# analog.net
KiCad netlist of a schematic drawn in EAGLE
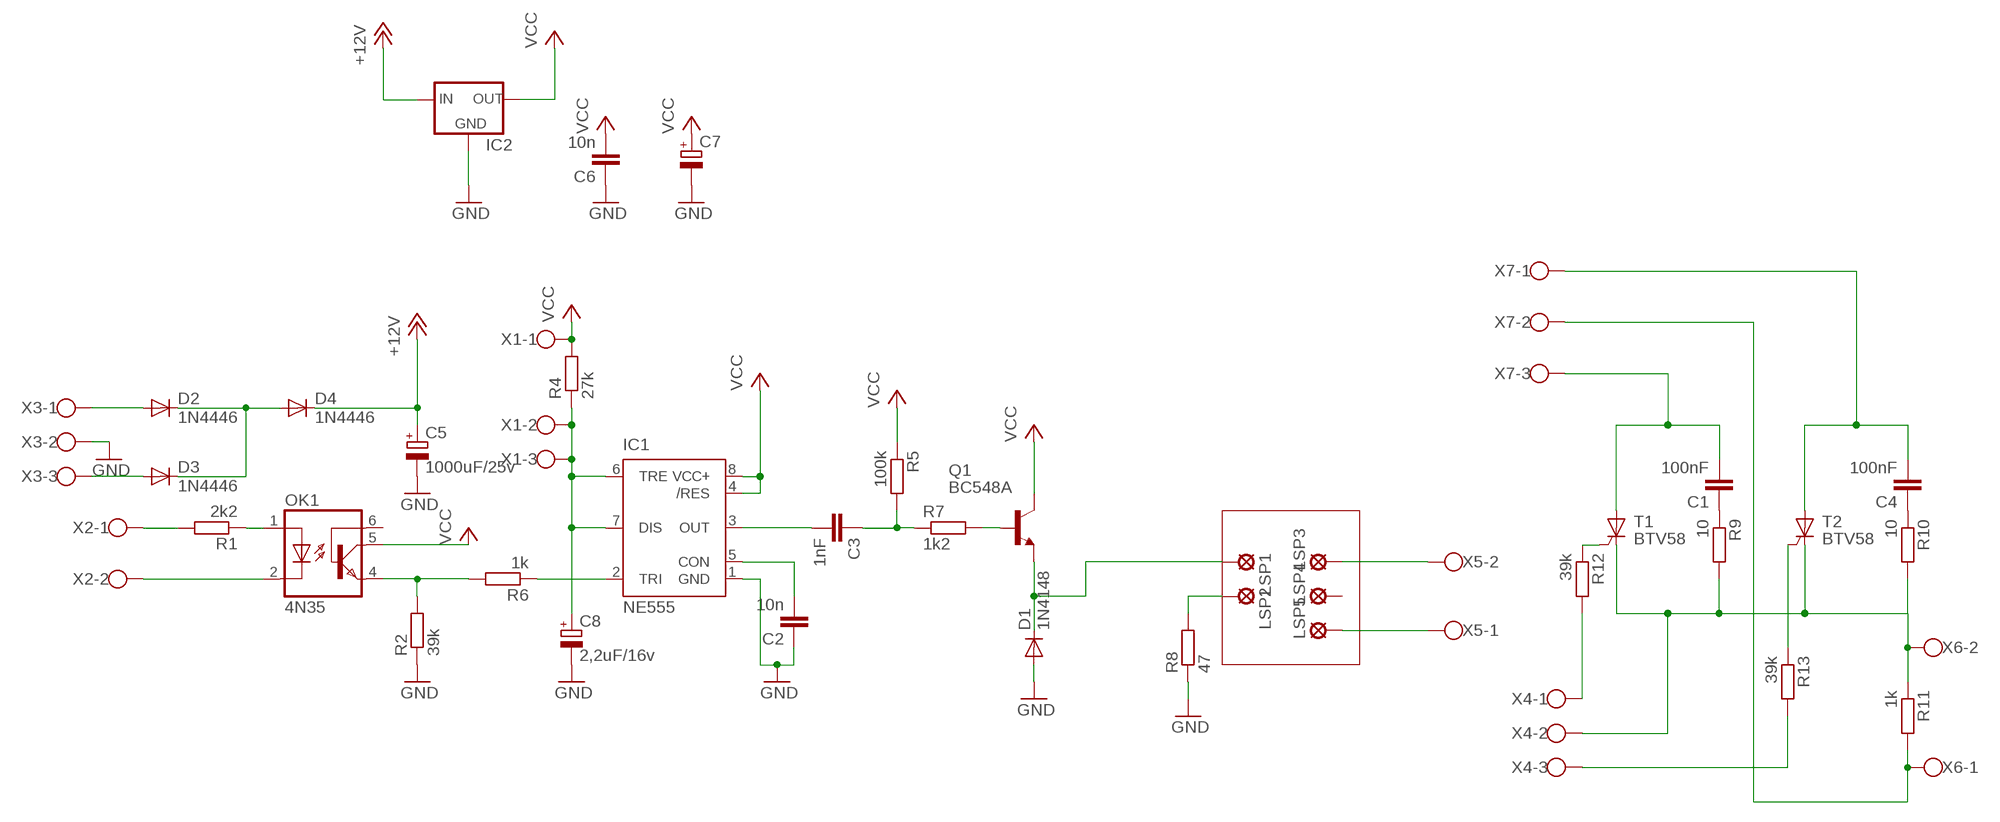
[diagram p0: schematic, sheet 1]

(export (version "E")
  (design (tool "Eeschema 10.0.6"))
  (components
    (comp (ref "C1")
      (value "100nF")
      (footprint "eagle-import:C050-025X075")
      (libsource (lib "eagle-import") (part "C-EU050-025X075"))
    )
    (comp (ref "C2")
      (value "10n")
      (footprint "eagle-import:C050-025X075")
      (libsource (lib "eagle-import") (part "C-EU050-025X075"))
    )
    (comp (ref "C3")
      (value "1nF")
      (footprint "eagle-import:C050-025X075")
      (libsource (lib "eagle-import") (part "C-EU050-025X075"))
    )
    (comp (ref "C4")
      (value "100nF")
      (footprint "eagle-import:C050-025X075")
      (libsource (lib "eagle-import") (part "C-EU050-025X075"))
    )
    (comp (ref "C5")
      (value "1000uF/25v")
      (footprint "eagle-import:E5-8,5")
      (libsource (lib "eagle-import") (part "CPOL-EUE5-8.5"))
    )
    (comp (ref "C6")
      (value "10n")
      (footprint "eagle-import:C050-025X075")
      (libsource (lib "eagle-import") (part "C-EU050-025X075"))
    )
    (comp (ref "C7")
      (value "CPOL-EUE2.5-5")
      (footprint "eagle-import:E2,5-5")
      (libsource (lib "eagle-import") (part "CPOL-EUE2.5-5"))
    )
    (comp (ref "C8")
      (value "2,2uF/16v")
      (footprint "eagle-import:E2,5-5")
      (libsource (lib "eagle-import") (part "CPOL-EUE2.5-5"))
    )
    (comp (ref "D1")
      (value "1N4148")
      (footprint "eagle-import:DO35-10")
      (libsource (lib "eagle-import") (part "1N4148DO35-10"))
    )
    (comp (ref "D2")
      (value "1N4446")
      (footprint "eagle-import:DO35-10")
      (libsource (lib "eagle-import") (part "1N4446"))
    )
    (comp (ref "D3")
      (value "1N4446")
      (footprint "eagle-import:DO35-10")
      (libsource (lib "eagle-import") (part "1N4446"))
    )
    (comp (ref "D4")
      (value "1N4446")
      (footprint "eagle-import:DO35-10")
      (libsource (lib "eagle-import") (part "1N4446"))
    )
    (comp (ref "IC1")
      (value "NE555")
      (footprint "eagle-import:DIL-08")
      (fields (field (name "MF") "Arrow Electronics") (field (name "MPN") "NE555N"))
      (libsource (lib "eagle-import") (part "NE555"))
    )
    (comp (ref "IC2")
      (value "78XXS")
      (footprint "eagle-import:78XXS")
      (libsource (lib "eagle-import") (part "78XXS"))
    )
    (comp (ref "LSP1")
      (value "MCS10B")
      (footprint "eagle-import:MCS10B")
      (libsource (lib "eagle-import") (part "MCS10B"))
    )
    (comp (ref "LSP2")
      (value "MCS10B")
      (footprint "eagle-import:MCS10B")
      (libsource (lib "eagle-import") (part "MCS10B"))
    )
    (comp (ref "LSP3")
      (value "MCS10B")
      (footprint "eagle-import:MCS10B")
      (libsource (lib "eagle-import") (part "MCS10B"))
    )
    (comp (ref "LSP4")
      (value "MCS10B")
      (footprint "eagle-import:MCS10B")
      (libsource (lib "eagle-import") (part "MCS10B"))
    )
    (comp (ref "LSP5")
      (value "MCS10B")
      (footprint "eagle-import:MCS10B")
      (libsource (lib "eagle-import") (part "MCS10B"))
    )
    (comp (ref "OK1")
      (value "4N35")
      (footprint "eagle-import:DIL06")
      (fields (field (name "MF") "FAIRCHILD SEMICONDUCTOR"))
      (libsource (lib "eagle-import") (part "4N35"))
    )
    (comp (ref "Q1")
      (value "BC548A")
      (footprint "eagle-import:TO92-EBC")
      (libsource (lib "eagle-import") (part "BC548A"))
    )
    (comp (ref "R1")
      (value "2k2")
      (footprint "eagle-import:0207_10")
      (libsource (lib "eagle-import") (part "R-EU_0207/10"))
    )
    (comp (ref "R2")
      (value "39k")
      (footprint "eagle-import:0207_10")
      (libsource (lib "eagle-import") (part "R-EU_0207/10"))
    )
    (comp (ref "R4")
      (value "27k")
      (footprint "eagle-import:0207_10")
      (libsource (lib "eagle-import") (part "R-EU_0207/10"))
    )
    (comp (ref "R5")
      (value "100k")
      (footprint "eagle-import:0207_10")
      (libsource (lib "eagle-import") (part "R-EU_0207/10"))
    )
    (comp (ref "R6")
      (value "1k")
      (footprint "eagle-import:0207_10")
      (libsource (lib "eagle-import") (part "R-EU_0207/10"))
    )
    (comp (ref "R7")
      (value "1k2")
      (footprint "eagle-import:0207_10")
      (libsource (lib "eagle-import") (part "R-EU_0207/10"))
    )
    (comp (ref "R8")
      (value "47")
      (footprint "eagle-import:0207_10")
      (libsource (lib "eagle-import") (part "R-EU_0207/10"))
    )
    (comp (ref "R9")
      (value "10")
      (footprint "eagle-import:0207_10")
      (libsource (lib "eagle-import") (part "R-EU_0207/10"))
    )
    (comp (ref "R10")
      (value "10")
      (footprint "eagle-import:0207_10")
      (libsource (lib "eagle-import") (part "R-EU_0207/10"))
    )
    (comp (ref "R11")
      (value "1k")
      (footprint "eagle-import:0207_10")
      (libsource (lib "eagle-import") (part "R-EU_0207/10"))
    )
    (comp (ref "R12")
      (value "39k")
      (footprint "eagle-import:0207_10")
      (libsource (lib "eagle-import") (part "R-EU_0207/10"))
    )
    (comp (ref "R13")
      (value "39k")
      (footprint "eagle-import:0207_10")
      (libsource (lib "eagle-import") (part "R-EU_0207/10"))
    )
    (comp (ref "T1")
      (value "BTV58")
      (footprint "eagle-import:TO220CS")
      (libsource (lib "eagle-import") (part "BTV58"))
    )
    (comp (ref "T2")
      (value "BTV58")
      (footprint "eagle-import:TO220CS")
      (libsource (lib "eagle-import") (part "BTV58"))
    )
    (comp (ref "X1")
      (value "W237-103")
      (footprint "eagle-import:W237-103")
      (fields (field (name "MPN") "237-103"))
      (libsource (lib "eagle-import") (part "W237-103"))
    )
    (comp (ref "X2")
      (value "W237-102")
      (footprint "eagle-import:W237-102")
      (fields (field (name "MPN") "237-102"))
      (libsource (lib "eagle-import") (part "W237-102"))
    )
    (comp (ref "X3")
      (value "W237-103")
      (footprint "eagle-import:W237-103")
      (fields (field (name "MPN") "237-103"))
      (libsource (lib "eagle-import") (part "W237-103"))
    )
    (comp (ref "X4")
      (value "W237-103")
      (footprint "eagle-import:W237-103")
      (fields (field (name "MPN") "237-103"))
      (libsource (lib "eagle-import") (part "W237-103"))
    )
    (comp (ref "X5")
      (value "W237-102")
      (footprint "eagle-import:W237-102")
      (fields (field (name "MPN") "237-102"))
      (libsource (lib "eagle-import") (part "W237-102"))
    )
    (comp (ref "X6")
      (value "W237-102")
      (footprint "eagle-import:W237-102")
      (fields (field (name "MPN") "237-102"))
      (libsource (lib "eagle-import") (part "W237-102"))
    )
    (comp (ref "X7")
      (value "W237-103")
      (footprint "eagle-import:W237-103")
      (fields (field (name "MPN") "237-103"))
      (libsource (lib "eagle-import") (part "W237-103"))
    )
  )
  (nets
    (net (code "1") (name "+12V") (class "Default")
      (node (ref "C5") (pin "+") (pinfunction "+_+") (pintype "passive"))
      (node (ref "D4") (pin "C") (pinfunction "C_C") (pintype "passive"))
      (node (ref "IC2") (pin "IN") (pinfunction "IN_IN") (pintype "input"))
    )
    (net (code "2") (name "GND") (class "Default")
      (node (ref "C2") (pin "1") (pinfunction "1_1") (pintype "passive"))
      (node (ref "C5") (pin "-") (pinfunction "-_-") (pintype "passive"))
      (node (ref "C6") (pin "1") (pinfunction "1_1") (pintype "passive"))
      (node (ref "C7") (pin "-") (pinfunction "-_-") (pintype "passive"))
      (node (ref "C8") (pin "-") (pinfunction "-_-") (pintype "passive"))
      (node (ref "D1") (pin "A") (pinfunction "A_A") (pintype "passive"))
      (node (ref "IC1") (pin "1") (pinfunction "GND_1") (pintype "power_in"))
      (node (ref "IC2") (pin "GND") (pinfunction "GND_GND") (pintype "input"))
      (node (ref "R2") (pin "1") (pinfunction "1_1") (pintype "passive"))
      (node (ref "R8") (pin "1") (pinfunction "1_1") (pintype "passive"))
      (node (ref "X3") (pin "2") (pinfunction "KL_2") (pintype "passive"))
    )
    (net (code "3") (name "Net-(C1-Pad1)") (class "Default")
      (node (ref "C1") (pin "1") (pinfunction "1_1") (pintype "passive"))
      (node (ref "R9") (pin "1") (pinfunction "1_1") (pintype "passive"))
    )
    (net (code "4") (name "Net-(C3-Pad1)") (class "Default")
      (node (ref "C3") (pin "1") (pinfunction "1_1") (pintype "passive"))
      (node (ref "R5") (pin "2") (pinfunction "2_2") (pintype "passive"))
      (node (ref "R7") (pin "1") (pinfunction "1_1") (pintype "passive"))
    )
    (net (code "5") (name "Net-(C4-Pad1)") (class "Default")
      (node (ref "C4") (pin "1") (pinfunction "1_1") (pintype "passive"))
      (node (ref "R10") (pin "1") (pinfunction "1_1") (pintype "passive"))
    )
    (net (code "6") (name "Net-(D1-PadC)") (class "Default")
      (node (ref "D1") (pin "C") (pinfunction "C_C") (pintype "passive"))
      (node (ref "LSP1") (pin "MP") (pinfunction "MP_MP") (pintype "passive"))
      (node (ref "Q1") (pin "E") (pinfunction "E_E") (pintype "passive"))
    )
    (net (code "7") (name "Net-(D2-PadC)") (class "Default")
      (node (ref "D2") (pin "C") (pinfunction "C_C") (pintype "passive"))
      (node (ref "D3") (pin "C") (pinfunction "C_C") (pintype "passive"))
      (node (ref "D4") (pin "A") (pinfunction "A_A") (pintype "passive"))
    )
    (net (code "8") (name "Net-(IC1-CON)") (class "Default")
      (node (ref "C2") (pin "2") (pinfunction "2_2") (pintype "passive"))
      (node (ref "IC1") (pin "5") (pinfunction "CON_5") (pintype "input"))
    )
    (net (code "9") (name "Net-(IC1-DIS)") (class "Default")
      (node (ref "C8") (pin "+") (pinfunction "+_+") (pintype "passive"))
      (node (ref "IC1") (pin "6") (pinfunction "TRE_6") (pintype "input"))
      (node (ref "IC1") (pin "7") (pinfunction "DIS_7") (pintype "input"))
      (node (ref "R4") (pin "1") (pinfunction "1_1") (pintype "passive"))
      (node (ref "X1") (pin "2") (pinfunction "KL_2") (pintype "passive"))
      (node (ref "X1") (pin "3") (pinfunction "KL_3") (pintype "passive"))
    )
    (net (code "10") (name "Net-(IC1-OUT)") (class "Default")
      (node (ref "C3") (pin "2") (pinfunction "2_2") (pintype "passive"))
      (node (ref "IC1") (pin "3") (pinfunction "OUT_3") (pintype "output"))
    )
    (net (code "11") (name "Net-(IC1-TRI)") (class "Default")
      (node (ref "IC1") (pin "2") (pinfunction "TRI_2") (pintype "input"))
      (node (ref "R6") (pin "1") (pinfunction "1_1") (pintype "passive"))
    )
    (net (code "12") (name "Net-(LSP2-PadMP)") (class "Default")
      (node (ref "LSP2") (pin "MP") (pinfunction "MP_MP") (pintype "passive"))
      (node (ref "R8") (pin "2") (pinfunction "2_2") (pintype "passive"))
    )
    (net (code "13") (name "Net-(OK1-A)") (class "Default")
      (node (ref "OK1") (pin "1") (pinfunction "A_1") (pintype "passive"))
      (node (ref "R1") (pin "1") (pinfunction "1_1") (pintype "passive"))
    )
    (net (code "14") (name "Net-(OK1-C)") (class "Default")
      (node (ref "OK1") (pin "2") (pinfunction "C_2") (pintype "passive"))
      (node (ref "X2") (pin "2") (pinfunction "KL_2") (pintype "passive"))
    )
    (net (code "15") (name "Net-(OK1-EMI)") (class "Default")
      (node (ref "OK1") (pin "4") (pinfunction "EMI_4") (pintype "passive"))
      (node (ref "R2") (pin "2") (pinfunction "2_2") (pintype "passive"))
      (node (ref "R6") (pin "2") (pinfunction "2_2") (pintype "passive"))
    )
    (net (code "16") (name "Net-(Q1-PadB)") (class "Default")
      (node (ref "Q1") (pin "B") (pinfunction "B_B") (pintype "passive"))
      (node (ref "R7") (pin "2") (pinfunction "2_2") (pintype "passive"))
    )
    (net (code "17") (name "Net-(R12-Pad1)") (class "Default")
      (node (ref "R12") (pin "1") (pinfunction "1_1") (pintype "passive"))
      (node (ref "T1") (pin "G") (pinfunction "G_G") (pintype "passive"))
    )
    (net (code "18") (name "Net-(R13-Pad1)") (class "Default")
      (node (ref "R13") (pin "1") (pinfunction "1_1") (pintype "passive"))
      (node (ref "T2") (pin "G") (pinfunction "G_G") (pintype "passive"))
    )
    (net (code "19") (name "Net-(X2A-KL)") (class "Default")
      (node (ref "R1") (pin "2") (pinfunction "2_2") (pintype "passive"))
      (node (ref "X2") (pin "1") (pinfunction "KL_1") (pintype "passive"))
    )
    (net (code "20") (name "Net-(X3A-KL)") (class "Default")
      (node (ref "D2") (pin "A") (pinfunction "A_A") (pintype "passive"))
      (node (ref "X3") (pin "1") (pinfunction "KL_1") (pintype "passive"))
    )
    (net (code "21") (name "Net-(X3C-KL)") (class "Default")
      (node (ref "D3") (pin "A") (pinfunction "A_A") (pintype "passive"))
      (node (ref "X3") (pin "3") (pinfunction "KL_3") (pintype "passive"))
    )
    (net (code "22") (name "Net-(X4A-KL)") (class "Default")
      (node (ref "R12") (pin "2") (pinfunction "2_2") (pintype "passive"))
      (node (ref "X4") (pin "1") (pinfunction "KL_1") (pintype "passive"))
    )
    (net (code "23") (name "Net-(X4B-KL)") (class "Default")
      (node (ref "R10") (pin "2") (pinfunction "2_2") (pintype "passive"))
      (node (ref "R11") (pin "1") (pinfunction "1_1") (pintype "passive"))
      (node (ref "R9") (pin "2") (pinfunction "2_2") (pintype "passive"))
      (node (ref "T1") (pin "C") (pinfunction "C_C") (pintype "passive"))
      (node (ref "T2") (pin "C") (pinfunction "C_C") (pintype "passive"))
      (node (ref "X4") (pin "2") (pinfunction "KL_2") (pintype "passive"))
      (node (ref "X6") (pin "2") (pinfunction "KL_2") (pintype "passive"))
    )
    (net (code "24") (name "Net-(X4C-KL)") (class "Default")
      (node (ref "R13") (pin "2") (pinfunction "2_2") (pintype "passive"))
      (node (ref "X4") (pin "3") (pinfunction "KL_3") (pintype "passive"))
    )
    (net (code "25") (name "Net-(X5A-KL)") (class "Default")
      (node (ref "LSP5") (pin "MP") (pinfunction "MP_MP") (pintype "passive"))
      (node (ref "X5") (pin "1") (pinfunction "KL_1") (pintype "passive"))
    )
    (net (code "26") (name "Net-(X5B-KL)") (class "Default")
      (node (ref "LSP3") (pin "MP") (pinfunction "MP_MP") (pintype "passive"))
      (node (ref "X5") (pin "2") (pinfunction "KL_2") (pintype "passive"))
    )
    (net (code "27") (name "Net-(X6A-KL)") (class "Default")
      (node (ref "R11") (pin "2") (pinfunction "2_2") (pintype "passive"))
      (node (ref "X6") (pin "1") (pinfunction "KL_1") (pintype "passive"))
      (node (ref "X7") (pin "2") (pinfunction "KL_2") (pintype "passive"))
    )
    (net (code "28") (name "Net-(X7A-KL)") (class "Default")
      (node (ref "C4") (pin "2") (pinfunction "2_2") (pintype "passive"))
      (node (ref "T2") (pin "A") (pinfunction "A_A") (pintype "passive"))
      (node (ref "X7") (pin "1") (pinfunction "KL_1") (pintype "passive"))
    )
    (net (code "29") (name "Net-(X7C-KL)") (class "Default")
      (node (ref "C1") (pin "2") (pinfunction "2_2") (pintype "passive"))
      (node (ref "T1") (pin "A") (pinfunction "A_A") (pintype "passive"))
      (node (ref "X7") (pin "3") (pinfunction "KL_3") (pintype "passive"))
    )
    (net (code "30") (name "VCC") (class "Default")
      (node (ref "C6") (pin "2") (pinfunction "2_2") (pintype "passive"))
      (node (ref "C7") (pin "+") (pinfunction "+_+") (pintype "passive"))
      (node (ref "IC1") (pin "4") (pinfunction "/RES_4") (pintype "input"))
      (node (ref "IC1") (pin "8") (pinfunction "VCC+_8") (pintype "power_in"))
      (node (ref "IC2") (pin "OUT") (pinfunction "OUT_OUT") (pintype "passive"))
      (node (ref "OK1") (pin "5") (pinfunction "COL_5") (pintype "passive"))
      (node (ref "Q1") (pin "C") (pinfunction "C_C") (pintype "passive"))
      (node (ref "R4") (pin "2") (pinfunction "2_2") (pintype "passive"))
      (node (ref "R5") (pin "1") (pinfunction "1_1") (pintype "passive"))
      (node (ref "X1") (pin "1") (pinfunction "KL_1") (pintype "passive"))
    )
    (net (code "31") (name "unconnected-(LSP4-PadMP)") (class "Default")
      (node (ref "LSP4") (pin "MP") (pinfunction "MP_MP") (pintype "passive"))
    )
    (net (code "32") (name "unconnected-(OK1-BAS-Pad6)") (class "Default")
      (node (ref "OK1") (pin "6") (pinfunction "BAS_6") (pintype "passive"))
    )
  )
)
